# Temp_Pressure.net
KiCad netlist of a schematic drawn in Altium Designer
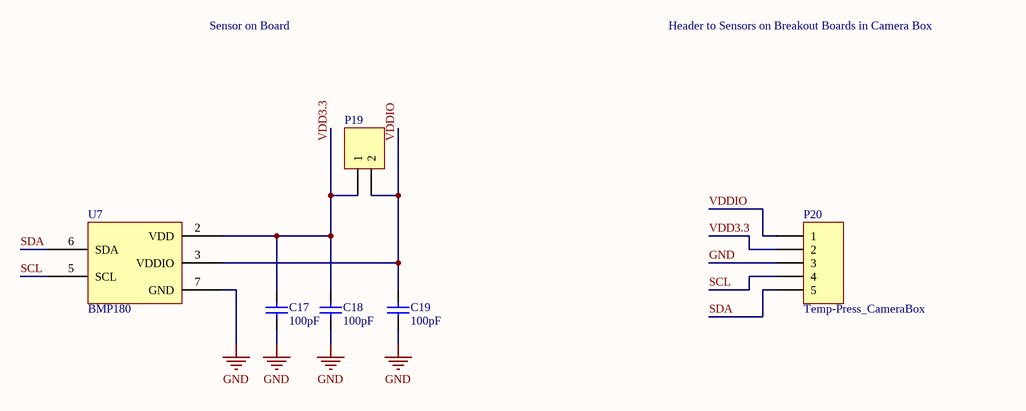
[diagram p0: Temp_Pressure.SchDoc]

(export (version "E")
  (design (tool "Eeschema 10.0.6"))
  (components
    (comp (ref "C17")
      (value "100pF")
      (footprint "C1206")
      (description "Capacitor (Semiconductor SIM Model)")
      (fields (field (name "Comment") "Cap Semi") (field (name "PUBLISHER") "Altium Limited"))
      (libsource (lib "Miscellaneous Devices") (part "Cap Semi"))
    )
    (comp (ref "C18")
      (value "100pF")
      (footprint "C1206")
      (description "Capacitor (Semiconductor SIM Model)")
      (fields (field (name "Comment") "Cap Semi") (field (name "PUBLISHER") "Altium Limited"))
      (libsource (lib "Miscellaneous Devices") (part "Cap Semi"))
    )
    (comp (ref "C19")
      (value "100pF")
      (footprint "C1206")
      (description "Capacitor (Semiconductor SIM Model)")
      (fields (field (name "Comment") "Cap Semi") (field (name "PUBLISHER") "Altium Limited"))
      (libsource (lib "Miscellaneous Devices") (part "Cap Semi"))
    )
    (comp (ref "P19")
      (value "Header 2")
      (footprint "HDR1X2")
      (description "Header, 2-Pin")
      (fields (field (name "PUBLISHER") "Altium Limited"))
      (libsource (lib "Miscellaneous Connectors") (part "Header 2"))
    )
    (comp (ref "P20")
      (value "Temp-Press_CameraBox")
      (footprint "HDR1X5")
      (description "Header, 5-Pin")
      (fields (field (name "PUBLISHER") "Altium Limited"))
      (libsource (lib "Miscellaneous Connectors") (part "Header 5"))
    )
    (comp (ref "U7") (value "BMP180") (footprint "BMP180") (libsource (lib "BMP180") (part "BMP180")))
  )
  (nets
    (net (code "1") (name "/SCL") (class "Default")
      (node (ref "P20") (pin "4") (pinfunction "4_4") (pintype "passive"))
      (node (ref "U7") (pin "5") (pinfunction "SCL_5") (pintype "passive"))
    )
    (net (code "2") (name "/SDA") (class "Default")
      (node (ref "P20") (pin "5") (pinfunction "5_5") (pintype "passive"))
      (node (ref "U7") (pin "6") (pinfunction "SDA_6") (pintype "passive"))
    )
    (net (code "3") (name "/VDD3.3") (class "Default")
      (node (ref "C17") (pin "2") (pinfunction "2_2") (pintype "passive"))
      (node (ref "C18") (pin "2") (pinfunction "2_2") (pintype "passive"))
      (node (ref "P19") (pin "1") (pinfunction "1_1") (pintype "passive"))
      (node (ref "P20") (pin "2") (pinfunction "2_2") (pintype "passive"))
      (node (ref "U7") (pin "2") (pinfunction "VDD_2") (pintype "passive"))
    )
    (net (code "4") (name "/VDDIO") (class "Default")
      (node (ref "C19") (pin "2") (pinfunction "2_2") (pintype "passive"))
      (node (ref "P19") (pin "2") (pinfunction "2_2") (pintype "passive"))
      (node (ref "P20") (pin "1") (pinfunction "1_1") (pintype "passive"))
      (node (ref "U7") (pin "3") (pinfunction "VDDIO_3") (pintype "passive"))
    )
    (net (code "5") (name "GND") (class "Default")
      (node (ref "C17") (pin "1") (pinfunction "1_1") (pintype "passive"))
      (node (ref "C18") (pin "1") (pinfunction "1_1") (pintype "passive"))
      (node (ref "C19") (pin "1") (pinfunction "1_1") (pintype "passive"))
      (node (ref "P20") (pin "3") (pinfunction "3_3") (pintype "passive"))
      (node (ref "U7") (pin "7") (pinfunction "GND_7") (pintype "passive"))
    )
  )
)
